# Smart_Plant_patch.net
KiCad netlist of a schematic drawn in EAGLE
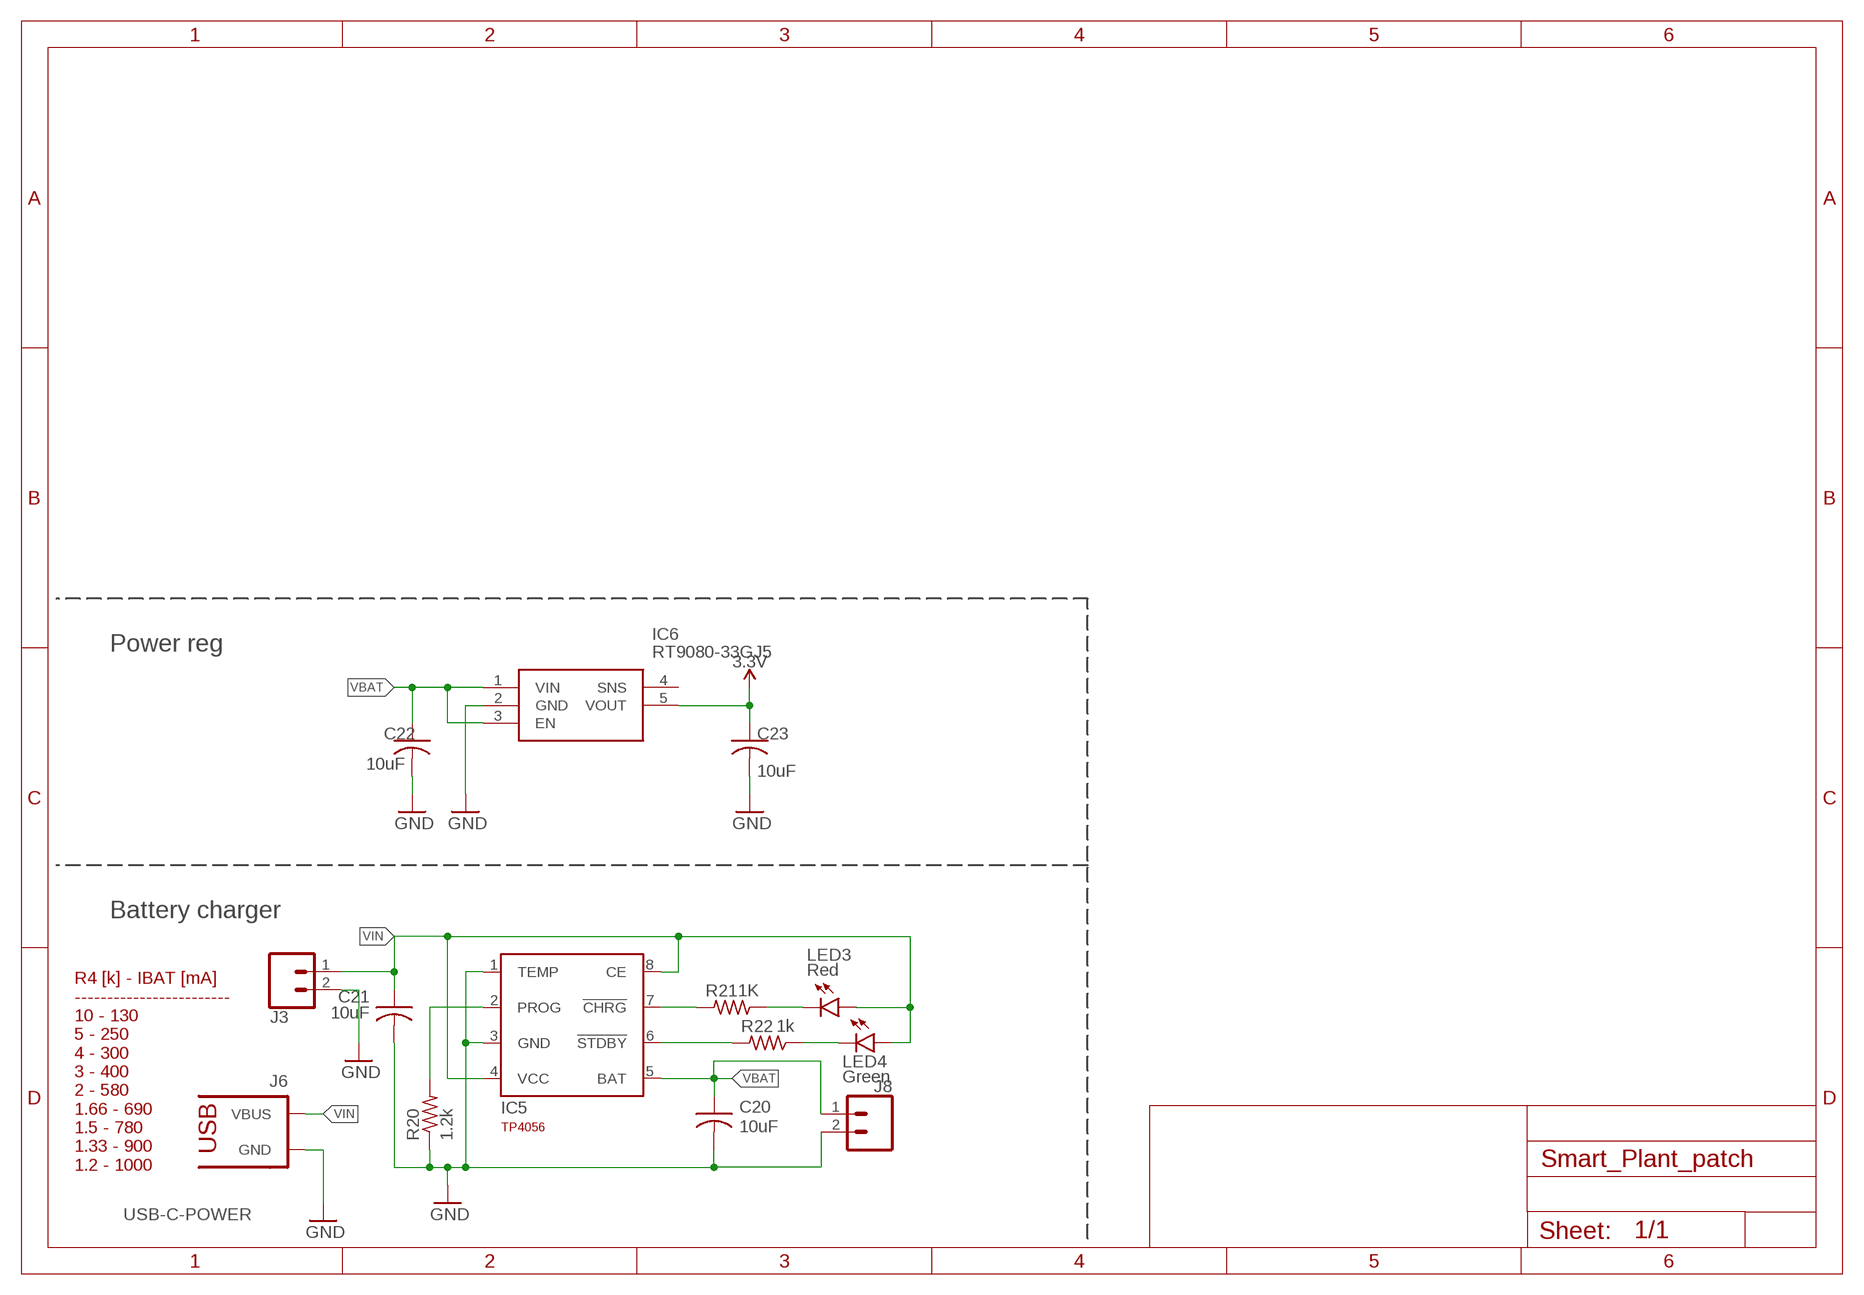
[diagram p0: schematic, sheet 1]

(export (version "E")
  (design (tool "Eeschema 10.0.6"))
  (components
    (comp (ref "C20")
      (value "10uF")
      (footprint "eagle-import:C0603")
      (libsource (lib "eagle-import") (part "C-USC0603"))
    )
    (comp (ref "C21")
      (value "10uF")
      (footprint "eagle-import:C0603")
      (libsource (lib "eagle-import") (part "C-USC0603"))
    )
    (comp (ref "C22")
      (value "10uF")
      (footprint "eagle-import:C0603")
      (libsource (lib "eagle-import") (part "C-USC0603"))
    )
    (comp (ref "C23")
      (value "10uF")
      (footprint "eagle-import:C0603")
      (libsource (lib "eagle-import") (part "C-USC0603"))
    )
    (comp (ref "IC5")
      (value "TP4056")
      (footprint "eagle-import:SOT23-8")
      (libsource (lib "eagle-import") (part "TP4056"))
    )
    (comp (ref "IC6")
      (value "RT9080-33GJ5")
      (footprint "eagle-import:SOT94P280X100-5N")
      (libsource (lib "eagle-import") (part "RT9080-33GJ5"))
    )
    (comp (ref "J3")
      (value "CONN_02")
      (footprint "eagle-import:1X02")
      (libsource (lib "eagle-import") (part "CONN_02"))
    )
    (comp (ref "J6")
      (value "USB-C-POWER")
      (footprint "eagle-import:USB-C-POWER")
      (libsource (lib "eagle-import") (part "USB-C-POWER"))
    )
    (comp (ref "J8")
      (value "CONN_02-JST-2MM-SMT")
      (footprint "eagle-import:JST-2-SMD")
      (libsource (lib "eagle-import") (part "CONN_02-JST-2MM-SMT"))
    )
    (comp (ref "LED3")
      (value "Red")
      (footprint "eagle-import:LED_0603")
      (libsource (lib "eagle-import") (part "LED0603"))
    )
    (comp (ref "LED4")
      (value "Green")
      (footprint "eagle-import:LED_0603")
      (libsource (lib "eagle-import") (part "LED0603"))
    )
    (comp (ref "R20")
      (value "1.2k")
      (footprint "eagle-import:R0603")
      (libsource (lib "eagle-import") (part "R-US_R0603"))
    )
    (comp (ref "R21")
      (value "1K")
      (footprint "eagle-import:R0603")
      (libsource (lib "eagle-import") (part "R-US_R0603"))
    )
    (comp (ref "R22")
      (value "1k")
      (footprint "eagle-import:R0603")
      (libsource (lib "eagle-import") (part "R-US_R0603"))
    )
  )
  (nets
    (net (code "1") (name "3.3V") (class "Default")
      (node (ref "C23") (pin "1") (pinfunction "1_1") (pintype "passive"))
      (node (ref "IC6") (pin "5") (pinfunction "VOUT_5") (pintype "bidirectional"))
    )
    (net (code "2") (name "GND") (class "Default")
      (node (ref "C20") (pin "2") (pinfunction "2_2") (pintype "passive"))
      (node (ref "C21") (pin "2") (pinfunction "2_2") (pintype "passive"))
      (node (ref "C22") (pin "2") (pinfunction "2_2") (pintype "passive"))
      (node (ref "C23") (pin "2") (pinfunction "2_2") (pintype "passive"))
      (node (ref "IC5") (pin "1") (pinfunction "TEMP_1") (pintype "bidirectional"))
      (node (ref "IC5") (pin "3") (pinfunction "GND_3") (pintype "bidirectional"))
      (node (ref "IC6") (pin "2") (pinfunction "GND_2") (pintype "bidirectional"))
      (node (ref "J3") (pin "2") (pinfunction "2_2") (pintype "passive"))
      (node (ref "J6") (pin "GND") (pinfunction "GND_GND") (pintype "power_in"))
      (node (ref "J8") (pin "2") (pinfunction "1_2") (pintype "passive"))
      (node (ref "R20") (pin "1") (pinfunction "1_1") (pintype "passive"))
    )
    (net (code "3") (name "Net-(IC5-PROG)") (class "Default")
      (node (ref "IC5") (pin "2") (pinfunction "PROG_2") (pintype "bidirectional"))
      (node (ref "R20") (pin "2") (pinfunction "2_2") (pintype "passive"))
    )
    (net (code "4") (name "Net-(IC5-~{CHRG})") (class "Default")
      (node (ref "IC5") (pin "7") (pinfunction "~{CHRG}_7") (pintype "bidirectional"))
      (node (ref "R21") (pin "2") (pinfunction "2_2") (pintype "passive"))
    )
    (net (code "5") (name "Net-(IC5-~{STDBY})") (class "Default")
      (node (ref "IC5") (pin "6") (pinfunction "~{STDBY}_6") (pintype "bidirectional"))
      (node (ref "R22") (pin "2") (pinfunction "2_2") (pintype "passive"))
    )
    (net (code "6") (name "Net-(LED3-PadC)") (class "Default")
      (node (ref "LED3") (pin "C") (pinfunction "C_C") (pintype "passive"))
      (node (ref "R21") (pin "1") (pinfunction "1_1") (pintype "passive"))
    )
    (net (code "7") (name "Net-(LED4-PadC)") (class "Default")
      (node (ref "LED4") (pin "C") (pinfunction "C_C") (pintype "passive"))
      (node (ref "R22") (pin "1") (pinfunction "1_1") (pintype "passive"))
    )
    (net (code "8") (name "VBAT") (class "Default")
      (node (ref "C20") (pin "1") (pinfunction "1_1") (pintype "passive"))
      (node (ref "C22") (pin "1") (pinfunction "1_1") (pintype "passive"))
      (node (ref "IC5") (pin "5") (pinfunction "BAT_5") (pintype "bidirectional"))
      (node (ref "IC6") (pin "1") (pinfunction "VIN_1") (pintype "bidirectional"))
      (node (ref "IC6") (pin "3") (pinfunction "EN_3") (pintype "bidirectional"))
      (node (ref "J8") (pin "1") (pinfunction "2_1") (pintype "passive"))
    )
    (net (code "9") (name "VIN") (class "Default")
      (node (ref "C21") (pin "1") (pinfunction "1_1") (pintype "passive"))
      (node (ref "IC5") (pin "4") (pinfunction "VCC_4") (pintype "bidirectional"))
      (node (ref "IC5") (pin "8") (pinfunction "CE_8") (pintype "bidirectional"))
      (node (ref "J3") (pin "1") (pinfunction "1_1") (pintype "passive"))
      (node (ref "J6") (pin "VBUS") (pinfunction "VBUS_VBUS") (pintype "power_in"))
      (node (ref "LED3") (pin "A") (pinfunction "A_A") (pintype "passive"))
      (node (ref "LED4") (pin "A") (pinfunction "A_A") (pintype "passive"))
    )
    (net (code "10") (name "unconnected-(IC6-SNS-Pad4)") (class "Default")
      (node (ref "IC6") (pin "4") (pinfunction "SNS_4") (pintype "bidirectional"))
    )
  )
)
